# digital_input_protection.net
KiCad netlist of a schematic drawn in Altium Designer
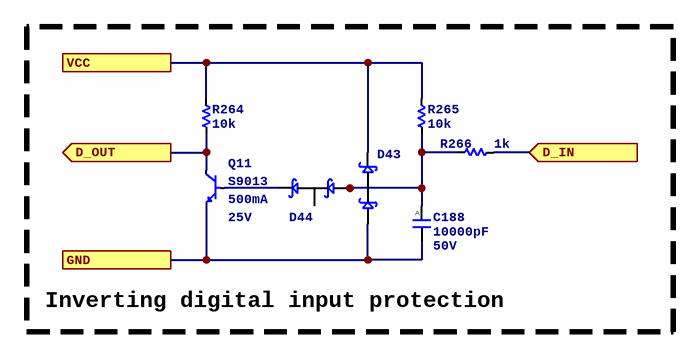
[diagram p0: digital_input_protection.SchDoc]

(export (version "E")
  (design (tool "Eeschema 10.0.6"))
  (components
    (comp (ref "C188")
      (value "CGJ2B3X7R1H103K050BB")
      (footprint "C0402_0.50MM")
      (description "CAP CER 10000PF 50V X7R 0402")
      (fields
        (field (name "CAPACITANCE") "10000pF")
        (field (name "VOLTAGE - RATED") "50V")
        (field (name "TOLERANCE") "±10%")
        (field (name "MANUFACTURER") "TDK Corporation")
      )
      (libsource (lib "sscp") (part "__template_cap_auto"))
    )
    (comp (ref "D43")
      (value "BAT54SLT1G")
      (footprint "3SOT23")
      (description "DIODE SCHOTTKY DUAL 30V SOT23")
      (fields (field (name "MANUFACTURER") "ON Semiconductor"))
      (libsource (lib "SSCP") (part "SCHOTTKY_30V_DUAL_BAT54SLT1G"))
    )
    (comp (ref "D44")
      (value "BAT54SLT1G")
      (footprint "3SOT23")
      (description "DIODE SCHOTTKY DUAL 30V SOT23")
      (fields (field (name "MANUFACTURER") "ON Semiconductor"))
      (libsource (lib "SSCP") (part "SCHOTTKY_30V_DUAL_BAT54SLT1G"))
    )
    (comp (ref "Q11")
      (value "S9013")
      (footprint "3SOT23")
      (description "Bipolar (BJT) Transistor NPN 25 V 500 mA 150MHz 300 mW Surface Mount SOT-23")
      (fields
        (field (name "MANUFACTURER") "Shenzhen Slkormicro Semicon Co., Ltd.")
        (field (name "CURRENT") "500mA")
        (field (name "VOLTAGE") "25V")
      )
      (libsource (lib "SSCP") (part "NPN_25V_S9013"))
    )
    (comp (ref "R264")
      (value "ERJ-2RKF1002X")
      (footprint "R0402_0.40MM")
      (description "RES SMD 10K OHM 1% 1/10W 0402")
      (fields
        (field (name "RESISTANCE") "10k")
        (field (name "TOLERANCE") "±1%")
        (field (name "MANUFACTURER") "Panasonic Electronic Components")
      )
      (libsource (lib "sscp") (part "__template_resistor"))
    )
    (comp (ref "R265")
      (value "ERJ-2RKF1002X")
      (footprint "R0402_0.40MM")
      (description "RES SMD 10K OHM 1% 1/10W 0402")
      (fields
        (field (name "RESISTANCE") "10k")
        (field (name "TOLERANCE") "±1%")
        (field (name "MANUFACTURER") "Panasonic Electronic Components")
      )
      (libsource (lib "sscp") (part "__template_resistor"))
    )
    (comp (ref "R266")
      (value "ERJ-2RKF1001X")
      (footprint "R0402_0.40MM")
      (description "RES SMD 1K OHM 1% 1/10W 0402")
      (fields
        (field (name "RESISTANCE") "1k")
        (field (name "TOLERANCE") "±1%")
        (field (name "MANUFACTURER") "Panasonic Electronic Components")
      )
      (libsource (lib "sscp") (part "__template_resistor"))
    )
  )
  (nets
    (net (code "1") (name "/D_IN") (class "Default") (node (ref "R266") (pin "1") (pintype "passive")))
    (net (code "2") (name "/D_OUT") (class "Default")
      (node (ref "Q11") (pin "3") (pinfunction "C_3") (pintype "passive"))
      (node (ref "R264") (pin "1") (pintype "passive"))
    )
    (net (code "3") (name "/GND") (class "Default")
      (node (ref "C188") (pin "2") (pintype "passive"))
      (node (ref "D43") (pin "1") (pintype "passive"))
      (node (ref "Q11") (pin "2") (pinfunction "E_2") (pintype "passive"))
    )
    (net (code "4") (name "/VCC") (class "Default")
      (node (ref "D43") (pin "2") (pintype "passive"))
      (node (ref "R264") (pin "2") (pintype "passive"))
      (node (ref "R265") (pin "2") (pintype "passive"))
    )
    (net (code "5") (name "Net-(C188-Pad1)") (class "Default")
      (node (ref "C188") (pin "1") (pintype "passive"))
      (node (ref "D43") (pin "3") (pintype "passive"))
      (node (ref "D44") (pin "1") (pintype "passive"))
      (node (ref "R265") (pin "1") (pintype "passive"))
      (node (ref "R266") (pin "2") (pintype "passive"))
    )
    (net (code "6") (name "Net-(Q11-B)") (class "Default")
      (node (ref "D44") (pin "2") (pintype "passive"))
      (node (ref "Q11") (pin "1") (pinfunction "B_1") (pintype "passive"))
    )
    (net (code "7") (name "unconnected-(D44-Pad3)") (class "Default")
      (node (ref "D44") (pin "3") (pintype "passive"))
    )
  )
)
